# rcz80cpuv2.net
KiCad netlist of a schematic drawn in EAGLE
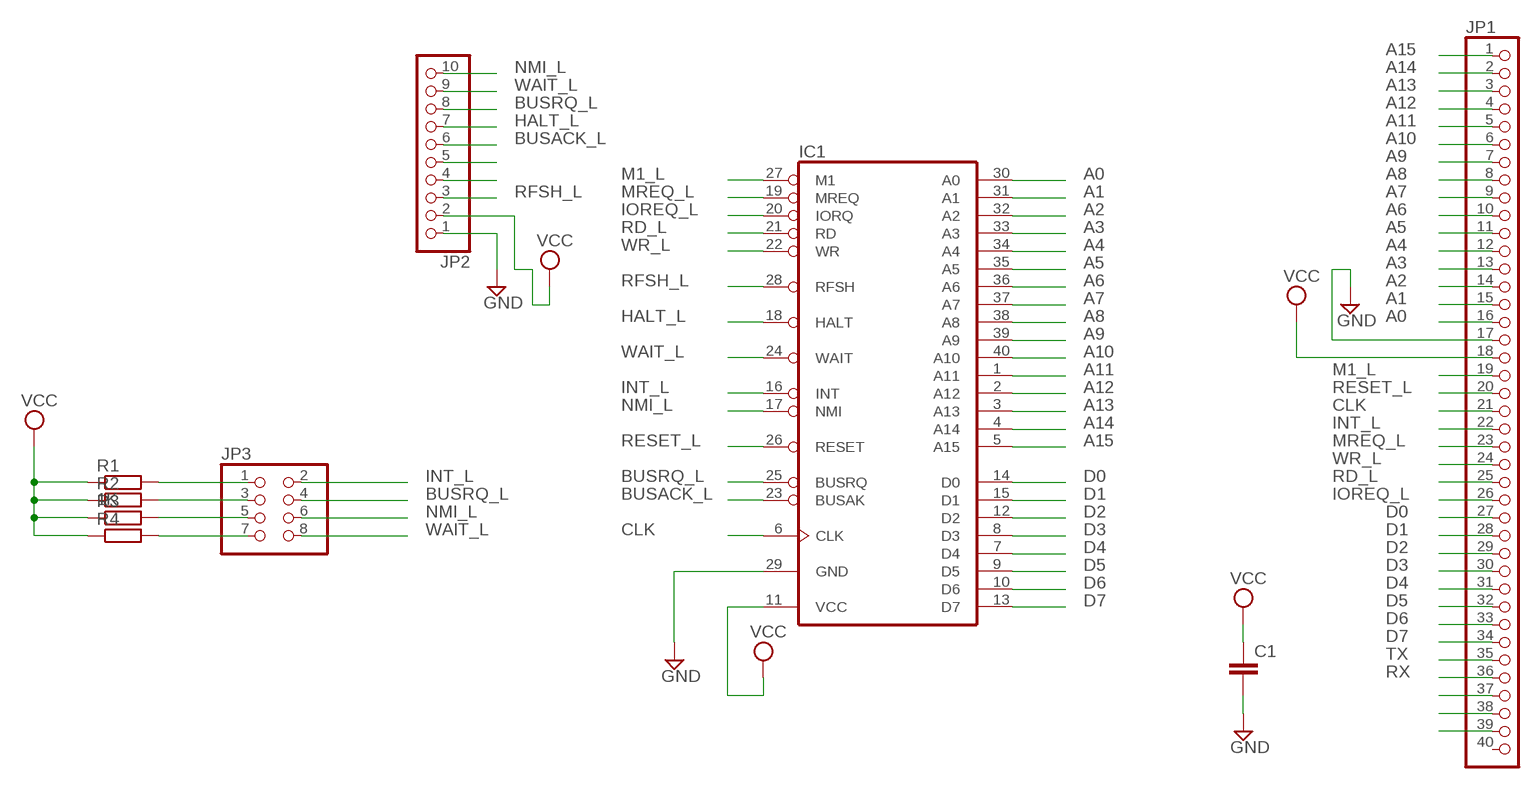
[diagram p0: schematic, sheet 1]

(export (version "E")
  (design (tool "Eeschema 10.0.6"))
  (components
    (comp (ref "C1")
      (value "C-EU025-024X044")
      (footprint "eagle-import:C025-024X044")
      (libsource (lib "eagle-import") (part "C-EU025-024X044"))
    )
    (comp (ref "IC1")
      (value "Z80CPU")
      (footprint "eagle-import:DIL40")
      (libsource (lib "eagle-import") (part "Z80CPU"))
    )
    (comp (ref "JP1")
      (value "PINHD-1X40")
      (footprint "eagle-import:1X40")
      (libsource (lib "eagle-import") (part "PINHD-1X40"))
    )
    (comp (ref "JP2")
      (value "PINHD-1X10")
      (footprint "eagle-import:1X10")
      (libsource (lib "eagle-import") (part "PINHD-1X10"))
    )
    (comp (ref "JP3")
      (value "PINHD-2X4")
      (footprint "eagle-import:2X04")
      (libsource (lib "eagle-import") (part "PINHD-2X4"))
    )
    (comp (ref "R1")
      (value "1K")
      (footprint "eagle-import:0204_7")
      (libsource (lib "eagle-import") (part "R-EU_0204/7"))
    )
    (comp (ref "R2")
      (value "R-EU_0204/7")
      (footprint "eagle-import:0204_7")
      (libsource (lib "eagle-import") (part "R-EU_0204/7"))
    )
    (comp (ref "R3")
      (value "R-EU_0204/7")
      (footprint "eagle-import:0204_7")
      (libsource (lib "eagle-import") (part "R-EU_0204/7"))
    )
    (comp (ref "R4")
      (value "R-EU_0204/7")
      (footprint "eagle-import:0204_7")
      (libsource (lib "eagle-import") (part "R-EU_0204/7"))
    )
  )
  (nets
    (net (code "1") (name "/A0") (class "Default")
      (node (ref "IC1") (pin "30") (pinfunction "A0_30") (pintype "output"))
      (node (ref "JP1") (pin "16") (pinfunction "16_16") (pintype "passive"))
    )
    (net (code "2") (name "/A1") (class "Default")
      (node (ref "IC1") (pin "31") (pinfunction "A1_31") (pintype "output"))
      (node (ref "JP1") (pin "15") (pinfunction "15_15") (pintype "passive"))
    )
    (net (code "3") (name "/A2") (class "Default")
      (node (ref "IC1") (pin "32") (pinfunction "A2_32") (pintype "output"))
      (node (ref "JP1") (pin "14") (pinfunction "14_14") (pintype "passive"))
    )
    (net (code "4") (name "/A3") (class "Default")
      (node (ref "IC1") (pin "33") (pinfunction "A3_33") (pintype "output"))
      (node (ref "JP1") (pin "13") (pinfunction "13_13") (pintype "passive"))
    )
    (net (code "5") (name "/A4") (class "Default")
      (node (ref "IC1") (pin "34") (pinfunction "A4_34") (pintype "output"))
      (node (ref "JP1") (pin "12") (pinfunction "12_12") (pintype "passive"))
    )
    (net (code "6") (name "/A5") (class "Default")
      (node (ref "IC1") (pin "35") (pinfunction "A5_35") (pintype "output"))
      (node (ref "JP1") (pin "11") (pinfunction "11_11") (pintype "passive"))
    )
    (net (code "7") (name "/A6") (class "Default")
      (node (ref "IC1") (pin "36") (pinfunction "A6_36") (pintype "output"))
      (node (ref "JP1") (pin "10") (pinfunction "10_10") (pintype "passive"))
    )
    (net (code "8") (name "/A7") (class "Default")
      (node (ref "IC1") (pin "37") (pinfunction "A7_37") (pintype "output"))
      (node (ref "JP1") (pin "9") (pinfunction "9_9") (pintype "passive"))
    )
    (net (code "9") (name "/A8") (class "Default")
      (node (ref "IC1") (pin "38") (pinfunction "A8_38") (pintype "output"))
      (node (ref "JP1") (pin "8") (pinfunction "8_8") (pintype "passive"))
    )
    (net (code "10") (name "/A9") (class "Default")
      (node (ref "IC1") (pin "39") (pinfunction "A9_39") (pintype "output"))
      (node (ref "JP1") (pin "7") (pinfunction "7_7") (pintype "passive"))
    )
    (net (code "11") (name "/A10") (class "Default")
      (node (ref "IC1") (pin "40") (pinfunction "A10_40") (pintype "output"))
      (node (ref "JP1") (pin "6") (pinfunction "6_6") (pintype "passive"))
    )
    (net (code "12") (name "/A11") (class "Default")
      (node (ref "IC1") (pin "1") (pinfunction "A11_1") (pintype "output"))
      (node (ref "JP1") (pin "5") (pinfunction "5_5") (pintype "passive"))
    )
    (net (code "13") (name "/A12") (class "Default")
      (node (ref "IC1") (pin "2") (pinfunction "A12_2") (pintype "output"))
      (node (ref "JP1") (pin "4") (pinfunction "4_4") (pintype "passive"))
    )
    (net (code "14") (name "/A13") (class "Default")
      (node (ref "IC1") (pin "3") (pinfunction "A13_3") (pintype "output"))
      (node (ref "JP1") (pin "3") (pinfunction "3_3") (pintype "passive"))
    )
    (net (code "15") (name "/A14") (class "Default")
      (node (ref "IC1") (pin "4") (pinfunction "A14_4") (pintype "output"))
      (node (ref "JP1") (pin "2") (pinfunction "2_2") (pintype "passive"))
    )
    (net (code "16") (name "/A15") (class "Default")
      (node (ref "IC1") (pin "5") (pinfunction "A15_5") (pintype "output"))
      (node (ref "JP1") (pin "1") (pinfunction "1_1") (pintype "passive"))
    )
    (net (code "17") (name "/BUSACK_L") (class "Default")
      (node (ref "IC1") (pin "23") (pinfunction "BUSAK_23") (pintype "output"))
      (node (ref "JP2") (pin "6") (pinfunction "6_6") (pintype "passive"))
    )
    (net (code "18") (name "/BUSRQ_L") (class "Default")
      (node (ref "IC1") (pin "25") (pinfunction "BUSRQ_25") (pintype "input"))
      (node (ref "JP2") (pin "8") (pinfunction "8_8") (pintype "passive"))
      (node (ref "JP3") (pin "4") (pinfunction "4_4") (pintype "passive"))
    )
    (net (code "19") (name "/CLK") (class "Default")
      (node (ref "IC1") (pin "6") (pinfunction "CLK_6") (pintype "input"))
      (node (ref "JP1") (pin "21") (pinfunction "21_21") (pintype "passive"))
    )
    (net (code "20") (name "/D0") (class "Default")
      (node (ref "IC1") (pin "14") (pinfunction "D0_14") (pintype "bidirectional"))
      (node (ref "JP1") (pin "27") (pinfunction "27_27") (pintype "passive"))
    )
    (net (code "21") (name "/D1") (class "Default")
      (node (ref "IC1") (pin "15") (pinfunction "D1_15") (pintype "bidirectional"))
      (node (ref "JP1") (pin "28") (pinfunction "28_28") (pintype "passive"))
    )
    (net (code "22") (name "/D2") (class "Default")
      (node (ref "IC1") (pin "12") (pinfunction "D2_12") (pintype "bidirectional"))
      (node (ref "JP1") (pin "29") (pinfunction "29_29") (pintype "passive"))
    )
    (net (code "23") (name "/D3") (class "Default")
      (node (ref "IC1") (pin "8") (pinfunction "D3_8") (pintype "bidirectional"))
      (node (ref "JP1") (pin "30") (pinfunction "30_30") (pintype "passive"))
    )
    (net (code "24") (name "/D4") (class "Default")
      (node (ref "IC1") (pin "7") (pinfunction "D4_7") (pintype "bidirectional"))
      (node (ref "JP1") (pin "31") (pinfunction "31_31") (pintype "passive"))
    )
    (net (code "25") (name "/D5") (class "Default")
      (node (ref "IC1") (pin "9") (pinfunction "D5_9") (pintype "bidirectional"))
      (node (ref "JP1") (pin "32") (pinfunction "32_32") (pintype "passive"))
    )
    (net (code "26") (name "/D6") (class "Default")
      (node (ref "IC1") (pin "10") (pinfunction "D6_10") (pintype "bidirectional"))
      (node (ref "JP1") (pin "33") (pinfunction "33_33") (pintype "passive"))
    )
    (net (code "27") (name "/D7") (class "Default")
      (node (ref "IC1") (pin "13") (pinfunction "D7_13") (pintype "bidirectional"))
      (node (ref "JP1") (pin "34") (pinfunction "34_34") (pintype "passive"))
    )
    (net (code "28") (name "/HALT_L") (class "Default")
      (node (ref "IC1") (pin "18") (pinfunction "HALT_18") (pintype "output"))
      (node (ref "JP2") (pin "7") (pinfunction "7_7") (pintype "passive"))
    )
    (net (code "29") (name "/INT_L") (class "Default")
      (node (ref "IC1") (pin "16") (pinfunction "INT_16") (pintype "input"))
      (node (ref "JP1") (pin "22") (pinfunction "22_22") (pintype "passive"))
      (node (ref "JP3") (pin "2") (pinfunction "2_2") (pintype "passive"))
    )
    (net (code "30") (name "/IOREQ_L") (class "Default")
      (node (ref "IC1") (pin "20") (pinfunction "IORQ_20") (pintype "output"))
      (node (ref "JP1") (pin "26") (pinfunction "26_26") (pintype "passive"))
    )
    (net (code "31") (name "/M1_L") (class "Default")
      (node (ref "IC1") (pin "27") (pinfunction "M1_27") (pintype "output"))
      (node (ref "JP1") (pin "19") (pinfunction "19_19") (pintype "passive"))
    )
    (net (code "32") (name "/MREQ_L") (class "Default")
      (node (ref "IC1") (pin "19") (pinfunction "MREQ_19") (pintype "output"))
      (node (ref "JP1") (pin "23") (pinfunction "23_23") (pintype "passive"))
    )
    (net (code "33") (name "/NMI_L") (class "Default")
      (node (ref "IC1") (pin "17") (pinfunction "NMI_17") (pintype "input"))
      (node (ref "JP2") (pin "10") (pinfunction "10_10") (pintype "passive"))
      (node (ref "JP3") (pin "6") (pinfunction "6_6") (pintype "passive"))
    )
    (net (code "34") (name "/RD_L") (class "Default")
      (node (ref "IC1") (pin "21") (pinfunction "RD_21") (pintype "output"))
      (node (ref "JP1") (pin "25") (pinfunction "25_25") (pintype "passive"))
    )
    (net (code "35") (name "/RESET_L") (class "Default")
      (node (ref "IC1") (pin "26") (pinfunction "RESET_26") (pintype "input"))
      (node (ref "JP1") (pin "20") (pinfunction "20_20") (pintype "passive"))
    )
    (net (code "36") (name "/RFSH_L") (class "Default")
      (node (ref "IC1") (pin "28") (pinfunction "RFSH_28") (pintype "output"))
      (node (ref "JP2") (pin "3") (pinfunction "3_3") (pintype "passive"))
    )
    (net (code "37") (name "/RX") (class "Default")
      (node (ref "JP1") (pin "36") (pinfunction "36_36") (pintype "passive"))
    )
    (net (code "38") (name "/TX") (class "Default")
      (node (ref "JP1") (pin "35") (pinfunction "35_35") (pintype "passive"))
    )
    (net (code "39") (name "/WAIT_L") (class "Default")
      (node (ref "IC1") (pin "24") (pinfunction "WAIT_24") (pintype "input"))
      (node (ref "JP2") (pin "9") (pinfunction "9_9") (pintype "passive"))
      (node (ref "JP3") (pin "8") (pinfunction "8_8") (pintype "passive"))
    )
    (net (code "40") (name "/WR_L") (class "Default")
      (node (ref "IC1") (pin "22") (pinfunction "WR_22") (pintype "output"))
      (node (ref "JP1") (pin "24") (pinfunction "24_24") (pintype "passive"))
    )
    (net (code "41") (name "GND") (class "Default")
      (node (ref "C1") (pin "2") (pinfunction "2_2") (pintype "passive"))
      (node (ref "IC1") (pin "29") (pinfunction "GND_29") (pintype "power_in"))
      (node (ref "JP1") (pin "17") (pinfunction "17_17") (pintype "passive"))
      (node (ref "JP2") (pin "1") (pinfunction "1_1") (pintype "passive"))
    )
    (net (code "42") (name "Net-(JP3-Pad1)") (class "Default")
      (node (ref "JP3") (pin "1") (pinfunction "1_1") (pintype "passive"))
      (node (ref "R1") (pin "2") (pinfunction "2_2") (pintype "passive"))
    )
    (net (code "43") (name "Net-(JP3-Pad3)") (class "Default")
      (node (ref "JP3") (pin "3") (pinfunction "3_3") (pintype "passive"))
      (node (ref "R2") (pin "2") (pinfunction "2_2") (pintype "passive"))
    )
    (net (code "44") (name "Net-(JP3-Pad5)") (class "Default")
      (node (ref "JP3") (pin "5") (pinfunction "5_5") (pintype "passive"))
      (node (ref "R3") (pin "2") (pinfunction "2_2") (pintype "passive"))
    )
    (net (code "45") (name "Net-(JP3-Pad7)") (class "Default")
      (node (ref "JP3") (pin "7") (pinfunction "7_7") (pintype "passive"))
      (node (ref "R4") (pin "2") (pinfunction "2_2") (pintype "passive"))
    )
    (net (code "46") (name "VCC") (class "Default")
      (node (ref "C1") (pin "1") (pinfunction "1_1") (pintype "passive"))
      (node (ref "IC1") (pin "11") (pinfunction "VCC_11") (pintype "power_in"))
      (node (ref "JP1") (pin "18") (pinfunction "18_18") (pintype "passive"))
      (node (ref "JP2") (pin "2") (pinfunction "2_2") (pintype "passive"))
      (node (ref "R1") (pin "1") (pinfunction "1_1") (pintype "passive"))
      (node (ref "R2") (pin "1") (pinfunction "1_1") (pintype "passive"))
      (node (ref "R3") (pin "1") (pinfunction "1_1") (pintype "passive"))
      (node (ref "R4") (pin "1") (pinfunction "1_1") (pintype "passive"))
    )
    (net (code "47") (name "unconnected-(JP1-Pad37)") (class "Default")
      (node (ref "JP1") (pin "37") (pinfunction "37_37") (pintype "passive"))
    )
    (net (code "48") (name "unconnected-(JP1-Pad38)") (class "Default")
      (node (ref "JP1") (pin "38") (pinfunction "38_38") (pintype "passive"))
    )
    (net (code "49") (name "unconnected-(JP1-Pad39)") (class "Default")
      (node (ref "JP1") (pin "39") (pinfunction "39_39") (pintype "passive"))
    )
    (net (code "50") (name "unconnected-(JP1-Pad40)") (class "Default")
      (node (ref "JP1") (pin "40") (pinfunction "40_40") (pintype "passive"))
    )
    (net (code "51") (name "unconnected-(JP2-Pad4)") (class "Default")
      (node (ref "JP2") (pin "4") (pinfunction "4_4") (pintype "passive"))
    )
    (net (code "52") (name "unconnected-(JP2-Pad5)") (class "Default")
      (node (ref "JP2") (pin "5") (pinfunction "5_5") (pintype "passive"))
    )
  )
)
